# Smart-ePaper-TestBoard.net
KiCad netlist of a schematic drawn in EasyEDA Pro
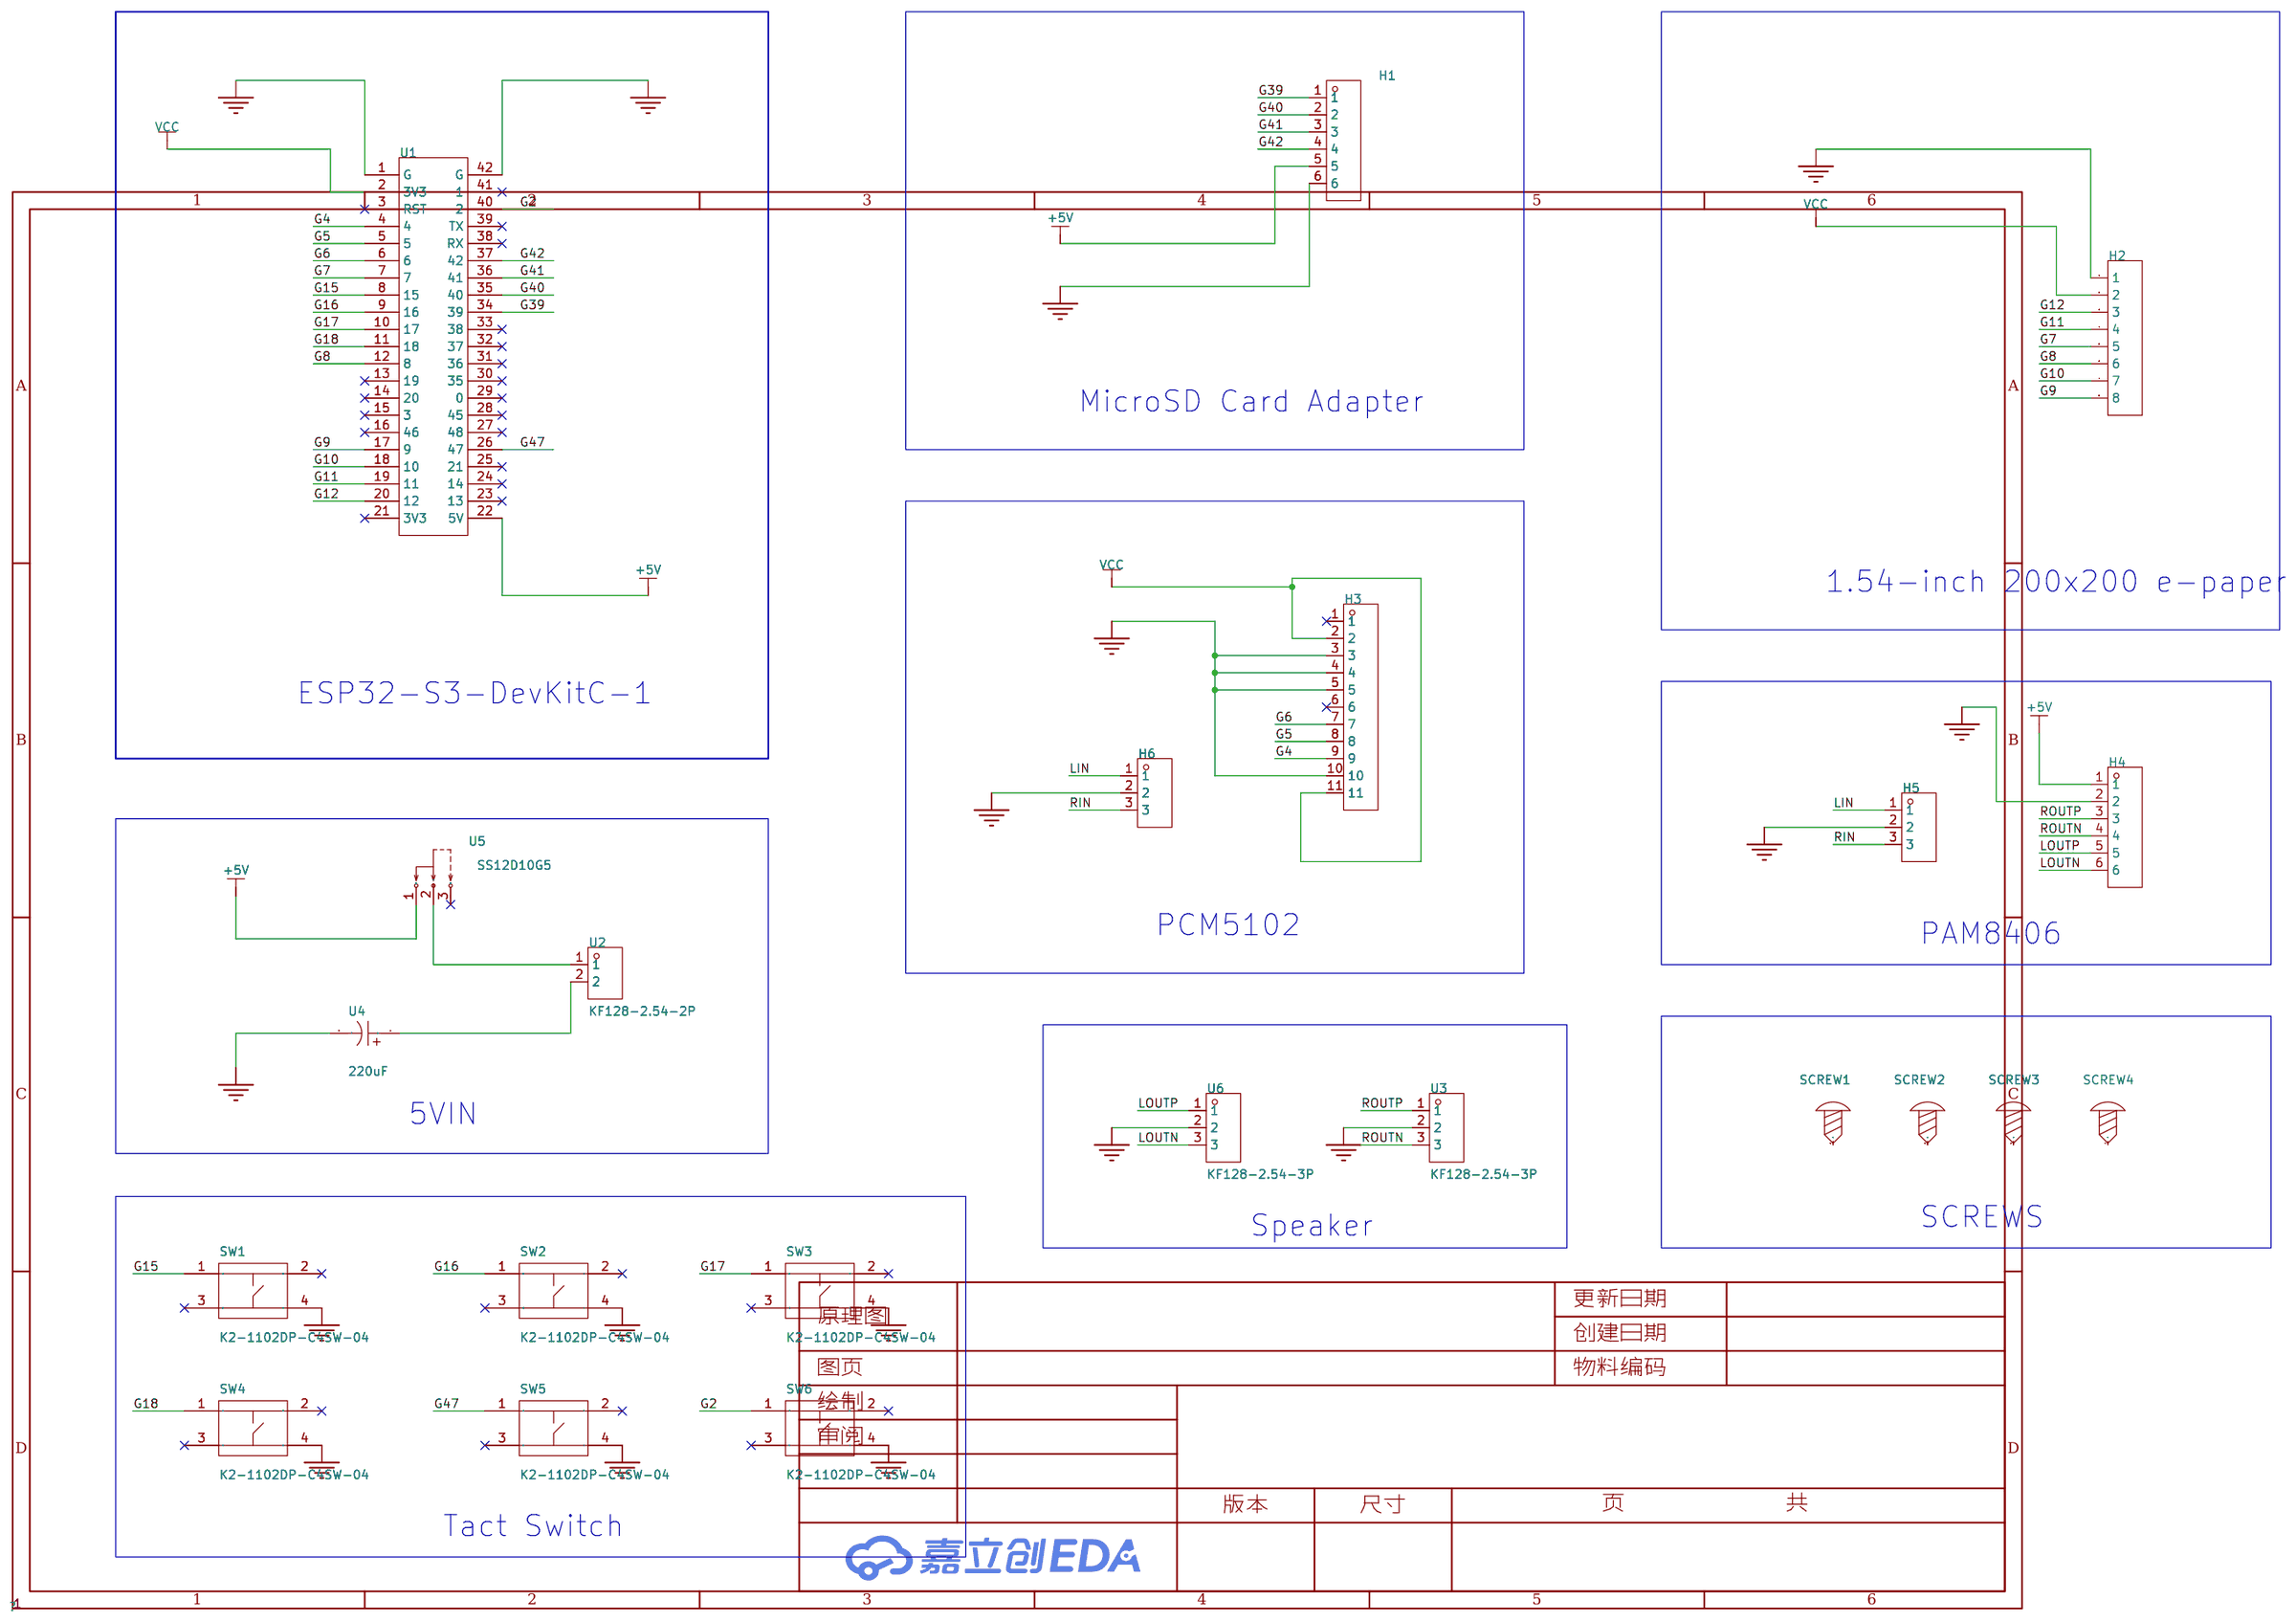
[diagram p0: schematic sheet]

(export (version "E")
  (design (tool "Eeschema 10.0.6"))
  (components
    (comp (ref "H1")
      (value "~")
      (footprint "easyedapro:HDR-TH_6P-P2.54-V-F")
      (libsource (lib "easyedapro") (part "Header-Female-2.54_1x6"))
    )
    (comp (ref "H2")
      (value "~")
      (footprint "easyedapro:HDR-TH_8P-P2.54-V-F-1")
      (libsource (lib "easyedapro") (part "Header-Female-2.54_1x8"))
    )
    (comp (ref "H3")
      (value "~")
      (footprint "easyedapro:HDR-TH_11P-P2.54-V-F")
      (libsource (lib "easyedapro") (part "HDR-F_2.54_1x11P"))
    )
    (comp (ref "H4")
      (value "~")
      (footprint "easyedapro:HDR-TH_6P-P2.54-V-F")
      (libsource (lib "easyedapro") (part "Header-Female-2.54_1x6"))
    )
    (comp (ref "H5")
      (value "~")
      (footprint "easyedapro:HDR-TH_3P-P2.54-V-F")
      (libsource (lib "easyedapro") (part "PM254V-11-03-H85"))
    )
    (comp (ref "H6")
      (value "~")
      (footprint "easyedapro:HDR-TH_3P-P2.54-V-F")
      (libsource (lib "easyedapro") (part "PM254V-11-03-H85"))
    )
    (comp (ref "SCREW1")
      (value "~")
      (footprint "easyedapro:M2螺丝")
      (libsource (lib "easyedapro") (part "螺丝孔"))
    )
    (comp (ref "SCREW2")
      (value "~")
      (footprint "easyedapro:M2螺丝")
      (libsource (lib "easyedapro") (part "螺丝孔"))
    )
    (comp (ref "SCREW3")
      (value "~")
      (footprint "easyedapro:M2螺丝")
      (libsource (lib "easyedapro") (part "螺丝孔"))
    )
    (comp (ref "SCREW4")
      (value "~")
      (footprint "easyedapro:M2螺丝")
      (libsource (lib "easyedapro") (part "螺丝孔"))
    )
    (comp (ref "SW1")
      (value "K2-1102DP-C4SW-04")
      (footprint "easyedapro:KEY-TH_4P-L6.0-W6.0-P4.50-LS6.50")
      (fields (field (name "Manufacturer") "韩国韩荣"))
      (libsource (lib "easyedapro") (part "K2-1102DP-C4SW-04"))
    )
    (comp (ref "SW2")
      (value "K2-1102DP-C4SW-04")
      (footprint "easyedapro:KEY-TH_4P-L6.0-W6.0-P4.50-LS6.50")
      (fields (field (name "Manufacturer") "韩国韩荣"))
      (libsource (lib "easyedapro") (part "K2-1102DP-C4SW-04"))
    )
    (comp (ref "SW3")
      (value "K2-1102DP-C4SW-04")
      (footprint "easyedapro:KEY-TH_4P-L6.0-W6.0-P4.50-LS6.50")
      (fields (field (name "Manufacturer") "韩国韩荣"))
      (libsource (lib "easyedapro") (part "K2-1102DP-C4SW-04"))
    )
    (comp (ref "SW4")
      (value "K2-1102DP-C4SW-04")
      (footprint "easyedapro:KEY-TH_4P-L6.0-W6.0-P4.50-LS6.50")
      (fields (field (name "Manufacturer") "韩国韩荣"))
      (libsource (lib "easyedapro") (part "K2-1102DP-C4SW-04"))
    )
    (comp (ref "SW5")
      (value "K2-1102DP-C4SW-04")
      (footprint "easyedapro:KEY-TH_4P-L6.0-W6.0-P4.50-LS6.50")
      (fields (field (name "Manufacturer") "韩国韩荣"))
      (libsource (lib "easyedapro") (part "K2-1102DP-C4SW-04"))
    )
    (comp (ref "SW6")
      (value "K2-1102DP-C4SW-04")
      (footprint "easyedapro:KEY-TH_4P-L6.0-W6.0-P4.50-LS6.50")
      (fields (field (name "Manufacturer") "韩国韩荣"))
      (libsource (lib "easyedapro") (part "K2-1102DP-C4SW-04"))
    )
    (comp (ref "U1")
      (value "~")
      (footprint "easyedapro:ESP32-S3-DevKitC-1")
      (libsource (lib "easyedapro") (part "ESP32-S3-DevKitC-1"))
    )
    (comp (ref "U2")
      (value "KF128-2.54-2P")
      (footprint "easyedapro:CONN-TH_P2.54_KF128-2.54-2P")
      (fields (field (name "Manufacturer") "KEFA(科发)"))
      (libsource (lib "easyedapro") (part "KF128-2.54-2P"))
    )
    (comp (ref "U3")
      (value "KF128-2.54-3P")
      (footprint "easyedapro:CONN-TH_3P-P2.54_KF128-2.54-3P")
      (fields (field (name "Manufacturer") "KEFA(科发)"))
      (libsource (lib "easyedapro") (part "KF128-2.54-3P"))
    )
    (comp (ref "U4")
      (value "220uF")
      (footprint "easyedapro:CAP-TH_BD6.3-P2.50-D0.5-FD")
      (description "容值:220uF;精度:±20%;额定电压:25V;纹波电流:236mA@120kHz;等效串联电阻:-;")
      (fields (field (name "Manufacturer Part") "KM1E221M0611") (field (name "Manufacturer") "ROQANG(容强)"))
      (libsource (lib "easyedapro") (part "km1e221m0611"))
    )
    (comp (ref "U5")
      (value "SS12D10G5")
      (footprint "easyedapro:SW-TH_SHOU-HAN_SS12D10G4")
      (description "电路结构:单刀双掷;安装方式:直插;额定电流(DC):2A;额定电压(DC):125V;机械寿命:3千次;")
      (fields (field (name "Manufacturer") "SHOU HAN(首韩)"))
      (libsource (lib "easyedapro") (part "SS12D10G5"))
    )
    (comp (ref "U6")
      (value "KF128-2.54-3P")
      (footprint "easyedapro:CONN-TH_3P-P2.54_KF128-2.54-3P")
      (fields (field (name "Manufacturer") "KEFA(科发)"))
      (libsource (lib "easyedapro") (part "KF128-2.54-3P"))
    )
  )
  (nets
    (net (code "1") (name "+5V") (class "Default")
      (node (ref "H1") (pin "5") (pinfunction "5_5") (pintype "unspecified"))
      (node (ref "H4") (pin "1") (pinfunction "1_1") (pintype "unspecified"))
      (node (ref "U1") (pin "22") (pinfunction "5V_22") (pintype "input"))
      (node (ref "U5") (pin "1") (pinfunction "1_1") (pintype "unspecified"))
    )
    (net (code "2") (name "/G2") (class "Default")
      (node (ref "SW6") (pin "1") (pinfunction "1_1") (pintype "unspecified"))
      (node (ref "U1") (pin "40") (pinfunction "2_40") (pintype "input"))
    )
    (net (code "3") (name "/G4") (class "Default")
      (node (ref "H3") (pin "9") (pinfunction "9_9") (pintype "input"))
      (node (ref "U1") (pin "4") (pinfunction "4_4") (pintype "input"))
    )
    (net (code "4") (name "/G5") (class "Default")
      (node (ref "H3") (pin "8") (pinfunction "8_8") (pintype "input"))
      (node (ref "U1") (pin "5") (pinfunction "5_5") (pintype "input"))
    )
    (net (code "5") (name "/G6") (class "Default")
      (node (ref "H3") (pin "7") (pinfunction "7_7") (pintype "input"))
      (node (ref "U1") (pin "6") (pinfunction "6_6") (pintype "input"))
    )
    (net (code "6") (name "/G7") (class "Default")
      (node (ref "H2") (pin "5") (pinfunction "5_5") (pintype "input"))
      (node (ref "U1") (pin "7") (pinfunction "7_7") (pintype "input"))
    )
    (net (code "7") (name "/G8") (class "Default")
      (node (ref "H2") (pin "6") (pinfunction "6_6") (pintype "input"))
      (node (ref "U1") (pin "12") (pinfunction "8_12") (pintype "input"))
    )
    (net (code "8") (name "/G9") (class "Default")
      (node (ref "H2") (pin "8") (pinfunction "8_8") (pintype "input"))
      (node (ref "U1") (pin "17") (pinfunction "9_17") (pintype "input"))
    )
    (net (code "9") (name "/G10") (class "Default")
      (node (ref "H2") (pin "7") (pinfunction "7_7") (pintype "input"))
      (node (ref "U1") (pin "18") (pinfunction "10_18") (pintype "input"))
    )
    (net (code "10") (name "/G11") (class "Default")
      (node (ref "H2") (pin "4") (pinfunction "4_4") (pintype "input"))
      (node (ref "U1") (pin "19") (pinfunction "11_19") (pintype "input"))
    )
    (net (code "11") (name "/G12") (class "Default")
      (node (ref "H2") (pin "3") (pinfunction "3_3") (pintype "input"))
      (node (ref "U1") (pin "20") (pinfunction "12_20") (pintype "input"))
    )
    (net (code "12") (name "/G15") (class "Default")
      (node (ref "SW1") (pin "1") (pinfunction "1_1") (pintype "unspecified"))
      (node (ref "U1") (pin "8") (pinfunction "15_8") (pintype "input"))
    )
    (net (code "13") (name "/G16") (class "Default")
      (node (ref "SW2") (pin "1") (pinfunction "1_1") (pintype "unspecified"))
      (node (ref "U1") (pin "9") (pinfunction "16_9") (pintype "input"))
    )
    (net (code "14") (name "/G17") (class "Default")
      (node (ref "SW3") (pin "1") (pinfunction "1_1") (pintype "unspecified"))
      (node (ref "U1") (pin "10") (pinfunction "17_10") (pintype "input"))
    )
    (net (code "15") (name "/G18") (class "Default")
      (node (ref "SW4") (pin "1") (pinfunction "1_1") (pintype "unspecified"))
      (node (ref "U1") (pin "11") (pinfunction "18_11") (pintype "input"))
    )
    (net (code "16") (name "/G39") (class "Default")
      (node (ref "H1") (pin "1") (pinfunction "1_1") (pintype "unspecified"))
      (node (ref "U1") (pin "34") (pinfunction "39_34") (pintype "input"))
    )
    (net (code "17") (name "/G40") (class "Default")
      (node (ref "H1") (pin "2") (pinfunction "2_2") (pintype "unspecified"))
      (node (ref "U1") (pin "35") (pinfunction "40_35") (pintype "input"))
    )
    (net (code "18") (name "/G41") (class "Default")
      (node (ref "H1") (pin "3") (pinfunction "3_3") (pintype "unspecified"))
      (node (ref "U1") (pin "36") (pinfunction "41_36") (pintype "input"))
    )
    (net (code "19") (name "/G42") (class "Default")
      (node (ref "H1") (pin "4") (pinfunction "4_4") (pintype "unspecified"))
      (node (ref "U1") (pin "37") (pinfunction "42_37") (pintype "input"))
    )
    (net (code "20") (name "/G47") (class "Default")
      (node (ref "SW5") (pin "1") (pinfunction "1_1") (pintype "unspecified"))
      (node (ref "U1") (pin "26") (pinfunction "47_26") (pintype "input"))
    )
    (net (code "21") (name "/LIN") (class "Default")
      (node (ref "H5") (pin "1") (pinfunction "1_1") (pintype "unspecified"))
      (node (ref "H6") (pin "1") (pinfunction "1_1") (pintype "unspecified"))
    )
    (net (code "22") (name "/LOUTN") (class "Default")
      (node (ref "H4") (pin "6") (pinfunction "6_6") (pintype "unspecified"))
      (node (ref "U6") (pin "3") (pinfunction "3_3") (pintype "unspecified"))
    )
    (net (code "23") (name "/LOUTP") (class "Default")
      (node (ref "H4") (pin "5") (pinfunction "5_5") (pintype "unspecified"))
      (node (ref "U6") (pin "1") (pinfunction "1_1") (pintype "unspecified"))
    )
    (net (code "24") (name "/RIN") (class "Default")
      (node (ref "H5") (pin "3") (pinfunction "3_3") (pintype "unspecified"))
      (node (ref "H6") (pin "3") (pinfunction "3_3") (pintype "unspecified"))
    )
    (net (code "25") (name "/ROUTN") (class "Default")
      (node (ref "H4") (pin "4") (pinfunction "4_4") (pintype "unspecified"))
      (node (ref "U3") (pin "3") (pinfunction "3_3") (pintype "unspecified"))
    )
    (net (code "26") (name "/ROUTP") (class "Default")
      (node (ref "H4") (pin "3") (pinfunction "3_3") (pintype "unspecified"))
      (node (ref "U3") (pin "1") (pinfunction "1_1") (pintype "unspecified"))
    )
    (net (code "27") (name "GND") (class "Default")
      (node (ref "H1") (pin "6") (pinfunction "6_6") (pintype "unspecified"))
      (node (ref "H2") (pin "1") (pinfunction "1_1") (pintype "input"))
      (node (ref "H3") (pin "10") (pinfunction "10_10") (pintype "input"))
      (node (ref "H3") (pin "3") (pinfunction "3_3") (pintype "input"))
      (node (ref "H3") (pin "4") (pinfunction "4_4") (pintype "input"))
      (node (ref "H3") (pin "5") (pinfunction "5_5") (pintype "input"))
      (node (ref "H4") (pin "2") (pinfunction "2_2") (pintype "unspecified"))
      (node (ref "H5") (pin "2") (pinfunction "2_2") (pintype "unspecified"))
      (node (ref "H6") (pin "2") (pinfunction "2_2") (pintype "unspecified"))
      (node (ref "SW1") (pin "4") (pinfunction "4_4") (pintype "unspecified"))
      (node (ref "SW2") (pin "4") (pinfunction "4_4") (pintype "unspecified"))
      (node (ref "SW3") (pin "4") (pinfunction "4_4") (pintype "unspecified"))
      (node (ref "SW4") (pin "4") (pinfunction "4_4") (pintype "unspecified"))
      (node (ref "SW5") (pin "4") (pinfunction "4_4") (pintype "unspecified"))
      (node (ref "SW6") (pin "4") (pinfunction "4_4") (pintype "unspecified"))
      (node (ref "U1") (pin "1") (pinfunction "G_1") (pintype "input"))
      (node (ref "U1") (pin "42") (pinfunction "G_42") (pintype "input"))
      (node (ref "U3") (pin "2") (pinfunction "2_2") (pintype "unspecified"))
      (node (ref "U4") (pin "2") (pinfunction "2_2") (pintype "input"))
      (node (ref "U6") (pin "2") (pinfunction "2_2") (pintype "unspecified"))
    )
    (net (code "28") (name "Net-(U2-Pad1)") (class "Default")
      (node (ref "U2") (pin "1") (pinfunction "1_1") (pintype "unspecified"))
      (node (ref "U5") (pin "2") (pinfunction "2_2") (pintype "unspecified"))
    )
    (net (code "29") (name "Net-(U2-Pad2)") (class "Default")
      (node (ref "U2") (pin "2") (pinfunction "2_2") (pintype "unspecified"))
      (node (ref "U4") (pin "1") (pinfunction "1_1") (pintype "input"))
    )
    (net (code "30") (name "VCC") (class "Default")
      (node (ref "H2") (pin "2") (pinfunction "2_2") (pintype "input"))
      (node (ref "H3") (pin "11") (pinfunction "11_11") (pintype "input"))
      (node (ref "H3") (pin "2") (pinfunction "2_2") (pintype "input"))
      (node (ref "U1") (pin "2") (pinfunction "3V3_2") (pintype "input"))
    )
    (net (code "31") (name "unconnected-(H3-Pad1)") (class "Default")
      (node (ref "H3") (pin "1") (pinfunction "1_1") (pintype "input+no_connect"))
    )
    (net (code "32") (name "unconnected-(H3-Pad6)") (class "Default")
      (node (ref "H3") (pin "6") (pinfunction "6_6") (pintype "input+no_connect"))
    )
    (net (code "33") (name "unconnected-(SCREW1-Pad1)") (class "Default")
      (node (ref "SCREW1") (pin "1") (pinfunction "1_1") (pintype "input"))
    )
    (net (code "34") (name "unconnected-(SCREW2-Pad1)") (class "Default")
      (node (ref "SCREW2") (pin "1") (pinfunction "1_1") (pintype "input"))
    )
    (net (code "35") (name "unconnected-(SCREW3-Pad1)") (class "Default")
      (node (ref "SCREW3") (pin "1") (pinfunction "1_1") (pintype "input"))
    )
    (net (code "36") (name "unconnected-(SCREW4-Pad1)") (class "Default")
      (node (ref "SCREW4") (pin "1") (pinfunction "1_1") (pintype "input"))
    )
    (net (code "37") (name "unconnected-(SW1-Pad2)") (class "Default")
      (node (ref "SW1") (pin "2") (pinfunction "2_2") (pintype "unspecified+no_connect"))
    )
    (net (code "38") (name "unconnected-(SW1-Pad3)") (class "Default")
      (node (ref "SW1") (pin "3") (pinfunction "3_3") (pintype "unspecified+no_connect"))
    )
    (net (code "39") (name "unconnected-(SW2-Pad2)") (class "Default")
      (node (ref "SW2") (pin "2") (pinfunction "2_2") (pintype "unspecified+no_connect"))
    )
    (net (code "40") (name "unconnected-(SW2-Pad3)") (class "Default")
      (node (ref "SW2") (pin "3") (pinfunction "3_3") (pintype "unspecified+no_connect"))
    )
    (net (code "41") (name "unconnected-(SW3-Pad2)") (class "Default")
      (node (ref "SW3") (pin "2") (pinfunction "2_2") (pintype "unspecified+no_connect"))
    )
    (net (code "42") (name "unconnected-(SW3-Pad3)") (class "Default")
      (node (ref "SW3") (pin "3") (pinfunction "3_3") (pintype "unspecified+no_connect"))
    )
    (net (code "43") (name "unconnected-(SW4-Pad2)") (class "Default")
      (node (ref "SW4") (pin "2") (pinfunction "2_2") (pintype "unspecified+no_connect"))
    )
    (net (code "44") (name "unconnected-(SW4-Pad3)") (class "Default")
      (node (ref "SW4") (pin "3") (pinfunction "3_3") (pintype "unspecified+no_connect"))
    )
    (net (code "45") (name "unconnected-(SW5-Pad2)") (class "Default")
      (node (ref "SW5") (pin "2") (pinfunction "2_2") (pintype "unspecified+no_connect"))
    )
    (net (code "46") (name "unconnected-(SW5-Pad3)") (class "Default")
      (node (ref "SW5") (pin "3") (pinfunction "3_3") (pintype "unspecified+no_connect"))
    )
    (net (code "47") (name "unconnected-(SW6-Pad2)") (class "Default")
      (node (ref "SW6") (pin "2") (pinfunction "2_2") (pintype "unspecified+no_connect"))
    )
    (net (code "48") (name "unconnected-(SW6-Pad3)") (class "Default")
      (node (ref "SW6") (pin "3") (pinfunction "3_3") (pintype "unspecified+no_connect"))
    )
    (net (code "49") (name "unconnected-(U1-0-Pad29)") (class "Default")
      (node (ref "U1") (pin "29") (pinfunction "0_29") (pintype "input+no_connect"))
    )
    (net (code "50") (name "unconnected-(U1-1-Pad41)") (class "Default")
      (node (ref "U1") (pin "41") (pinfunction "1_41") (pintype "input+no_connect"))
    )
    (net (code "51") (name "unconnected-(U1-3-Pad15)") (class "Default")
      (node (ref "U1") (pin "15") (pinfunction "3_15") (pintype "input+no_connect"))
    )
    (net (code "52") (name "unconnected-(U1-3V3-Pad21)") (class "Default")
      (node (ref "U1") (pin "21") (pinfunction "3V3_21") (pintype "input+no_connect"))
    )
    (net (code "53") (name "unconnected-(U1-13-Pad23)") (class "Default")
      (node (ref "U1") (pin "23") (pinfunction "13_23") (pintype "input+no_connect"))
    )
    (net (code "54") (name "unconnected-(U1-14-Pad24)") (class "Default")
      (node (ref "U1") (pin "24") (pinfunction "14_24") (pintype "input+no_connect"))
    )
    (net (code "55") (name "unconnected-(U1-19-Pad13)") (class "Default")
      (node (ref "U1") (pin "13") (pinfunction "19_13") (pintype "input+no_connect"))
    )
    (net (code "56") (name "unconnected-(U1-20-Pad14)") (class "Default")
      (node (ref "U1") (pin "14") (pinfunction "20_14") (pintype "input+no_connect"))
    )
    (net (code "57") (name "unconnected-(U1-21-Pad25)") (class "Default")
      (node (ref "U1") (pin "25") (pinfunction "21_25") (pintype "input+no_connect"))
    )
    (net (code "58") (name "unconnected-(U1-35-Pad30)") (class "Default")
      (node (ref "U1") (pin "30") (pinfunction "35_30") (pintype "input+no_connect"))
    )
    (net (code "59") (name "unconnected-(U1-36-Pad31)") (class "Default")
      (node (ref "U1") (pin "31") (pinfunction "36_31") (pintype "input+no_connect"))
    )
    (net (code "60") (name "unconnected-(U1-37-Pad32)") (class "Default")
      (node (ref "U1") (pin "32") (pinfunction "37_32") (pintype "input+no_connect"))
    )
    (net (code "61") (name "unconnected-(U1-38-Pad33)") (class "Default")
      (node (ref "U1") (pin "33") (pinfunction "38_33") (pintype "input+no_connect"))
    )
    (net (code "62") (name "unconnected-(U1-45-Pad28)") (class "Default")
      (node (ref "U1") (pin "28") (pinfunction "45_28") (pintype "input+no_connect"))
    )
    (net (code "63") (name "unconnected-(U1-46-Pad16)") (class "Default")
      (node (ref "U1") (pin "16") (pinfunction "46_16") (pintype "input+no_connect"))
    )
    (net (code "64") (name "unconnected-(U1-48-Pad27)") (class "Default")
      (node (ref "U1") (pin "27") (pinfunction "48_27") (pintype "input+no_connect"))
    )
    (net (code "65") (name "unconnected-(U1-RST-Pad3)") (class "Default")
      (node (ref "U1") (pin "3") (pinfunction "RST_3") (pintype "input+no_connect"))
    )
    (net (code "66") (name "unconnected-(U1-RX-Pad38)") (class "Default")
      (node (ref "U1") (pin "38") (pinfunction "RX_38") (pintype "input+no_connect"))
    )
    (net (code "67") (name "unconnected-(U1-TX-Pad39)") (class "Default")
      (node (ref "U1") (pin "39") (pinfunction "TX_39") (pintype "input+no_connect"))
    )
    (net (code "68") (name "unconnected-(U5-Pad3)") (class "Default")
      (node (ref "U5") (pin "3") (pinfunction "3_3") (pintype "unspecified+no_connect"))
    )
  )
)
